# USD_PD.net
KiCad netlist of a schematic drawn in Altium Designer
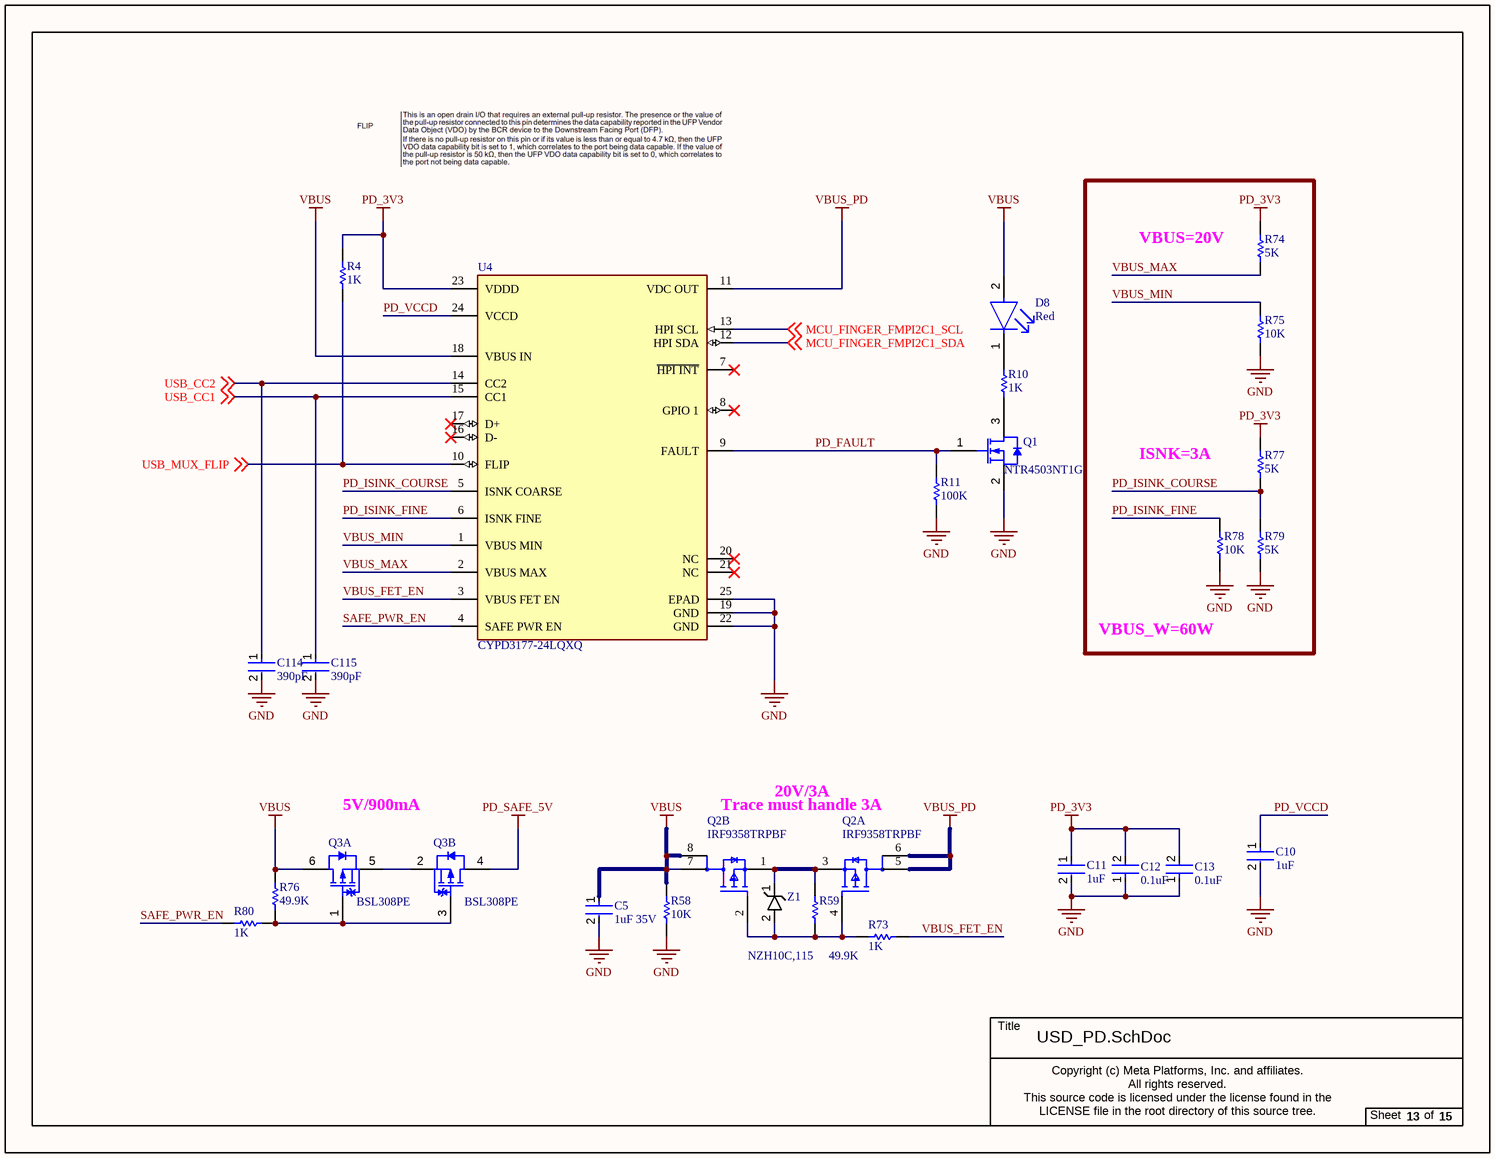
[diagram p0: USD_PD.SchDoc]

(export (version "E")
  (design (tool "Eeschema 10.0.6"))
  (components
    (comp (ref "C5")
      (value "1uF 35V")
      (footprint "FP-C1005-050-0_05-IPC_C")
      (description "Multilayer Ceramic Capacitors 1μF ±10% 35V X5R SMD 0402")
      (fields (field (name "TOLERANCE") "10%"))
      (libsource (lib "Altium Content Vault") (part "b4654b650e69147ec39a6b967a45e02"))
    )
    (comp (ref "C10")
      (value "1uF")
      (footprint "FP-CL511-IPC_C")
      (description "Cap Ceramic 1uF 10V X5R ±10% SMD 0402 +85°C Paper T/R")
      (fields (field (name "TOLERANCE") "10%"))
      (libsource (lib "Altium Content Vault") (part "b4654b650e69147ec39a6b967a45e02"))
    )
    (comp (ref "C11")
      (value "1uF")
      (footprint "FP-CL511-IPC_C")
      (description "Cap Ceramic 1uF 10V X5R ±10% SMD 0402 +85°C Paper T/R")
      (fields (field (name "TOLERANCE") "10%"))
      (libsource (lib "Altium Content Vault") (part "b4654b650e69147ec39a6b967a45e02"))
    )
    (comp (ref "C12")
      (value "0.1uF")
      (footprint "FP-CC0201-BA-MFG")
      (description "CAP CER 0.1UF 6.3V X5R 0201")
      (fields (field (name "MANUFACTURER") "Yageo") (field (name "TOLERANCE") "0.1"))
      (libsource (lib "Altium Content Vault") (part "11868f565c42a9108669ba33697ecf6"))
    )
    (comp (ref "C13")
      (value "0.1uF")
      (footprint "FP-CC0201-BA-MFG")
      (description "CAP CER 0.1UF 6.3V X5R 0201")
      (fields (field (name "MANUFACTURER") "Yageo") (field (name "TOLERANCE") "0.1"))
      (libsource (lib "Altium Content Vault") (part "11868f565c42a9108669ba33697ecf6"))
    )
    (comp (ref "C114")
      (value "390pF")
      (footprint "FP-C0402-BB-MFG")
      (description "CAP CER 390PF 50V C0G/NP0 0402")
      (fields
        (field (name "OCTOPART") "https://octopart.com/c0402c391j5gactu-kemet-13148117")
        (field (name "MANUFACTURER PART NUMBER") "C0402C391J5GACTU")
      )
      (libsource (lib "Altium Content Vault") (part "b4654b650e69147ec39a6b967a45e02"))
    )
    (comp (ref "C115")
      (value "390pF")
      (footprint "FP-C0402-BB-MFG")
      (description "CAP CER 390PF 50V C0G/NP0 0402")
      (fields
        (field (name "OCTOPART") "https://octopart.com/c0402c391j5gactu-kemet-13148117")
        (field (name "MANUFACTURER PART NUMBER") "C0402C391J5GACTU")
      )
      (libsource (lib "Altium Content Vault") (part "b4654b650e69147ec39a6b967a45e02"))
    )
    (comp (ref "D8")
      (value "Red")
      (footprint "FP-LTST-C190KRKT-MFG")
      (description "LED RED CLEAR CHIP SMD")
      (libsource (lib "Altium Content Vault") (part "8706943c75ba83719d021d2fdc84c58"))
    )
    (comp (ref "Q1")
      (value "NTR4503NT1G")
      (footprint "ONSC-SOT-23-3-318-08_V")
      (description "Power MOSFET, 30 V, 2.5 A, Single N-Channel, 3-Pin SOT-23, Pb-Free, Tape and Reel")
      (fields (field (name "MANUFACTURER") "On Semiconductor"))
      (libsource (lib "Altium Content Vault") (part "ONSC-NMOS-G1S2D3-3"))
    )
    (comp (ref "Q2")
      (value "IRF9358TRPBF")
      (footprint "FP-PG-DSO-8-IPC_A")
      (description "MOSFET 2P-CH 30V 9.2A 8SOIC")
      (libsource (lib "Altium Content Vault") (part "5e38728c795c682e8f1ce7f9b94c653"))
    )
    (comp (ref "Q3")
      (value "BSL308PE")
      (footprint "INF-PG-TSOP-6_N")
      (fields (field (name "MANUFACTURER") "Infineon"))
      (libsource (lib "Altium Content Vault") (part "INF-BSL3_2XX-PG-TSOP-6-6"))
    )
    (comp (ref "R4")
      (value "1K")
      (footprint "RESC1005X40X25NL05T05")
      (description "Chip Resistor, 1 KOhm, +/- 1%, 100 mW, -55 to 155 degC, 0402 (1005 Metric), RoHS, Tape and Reel")
      (fields (field (name "PARTNUMBER") "ERJ-2RKF1001X") (field (name "MANUFACTURER") "Basic Passives"))
      (libsource (lib "Altium Content Vault") (part "RES-2"))
    )
    (comp (ref "R10")
      (value "1K")
      (footprint "RESC1005X40X25NL05T05")
      (description "Chip Resistor, 1 KOhm, +/- 1%, 100 mW, -55 to 155 degC, 0402 (1005 Metric), RoHS, Tape and Reel")
      (fields (field (name "PARTNUMBER") "ERJ-2RKF1001X") (field (name "MANUFACTURER") "Basic Passives"))
      (libsource (lib "Altium Content Vault") (part "RES-2"))
    )
    (comp (ref "R11")
      (value "100K")
      (footprint "RESC1005X40X25NL05T10")
      (fields (field (name "PART NUMBER") "RC0402FR-07100KL") (field (name "MANUFACTURER") "Yageo / Phycomp"))
      (libsource (lib "Altium Content Vault") (part "RES"))
    )
    (comp (ref "R58")
      (value "10K")
      (footprint "RESC1005X40X25ML05T10")
      (fields (field (name "PART NUMBER") "CRCW040210K0FKEDHP") (field (name "MANUFACTURER") "Vishay Dale"))
      (libsource (lib "Altium Content Vault") (part "RES"))
    )
    (comp (ref "R59")
      (value "49.9K")
      (footprint "RESC1005X35X20LL05T10")
      (fields
        (field (name "PART NUMBER") "CPF0402B49K9E1")
        (field (name "MANUFACTURER") "TE Connectivity / AMP")
      )
      (libsource (lib "Altium Content Vault") (part "RES"))
    )
    (comp (ref "R73")
      (value "1K")
      (footprint "RESC1005X40X25NL05T05")
      (description "Chip Resistor, 1 KOhm, +/- 1%, 100 mW, -55 to 155 degC, 0402 (1005 Metric), RoHS, Tape and Reel")
      (fields (field (name "PARTNUMBER") "ERJ-2RKF1001X") (field (name "MANUFACTURER") "Basic Passives"))
      (libsource (lib "Altium Content Vault") (part "RES-2"))
    )
    (comp (ref "R74")
      (value "5K")
      (footprint "RESC1005X35X20LL05T10")
      (fields
        (field (name "MANUFACTURER") "TE Connectivity / AMP")
        (field (name "PART NUMBER") "CPF0402B5K1E1")
      )
      (libsource (lib "Altium Content Vault") (part "RES"))
    )
    (comp (ref "R75")
      (value "10K")
      (footprint "RESC1005X40X25ML05T10")
      (fields (field (name "PART NUMBER") "CRCW040210K0FKEDHP") (field (name "MANUFACTURER") "Vishay Dale"))
      (libsource (lib "Altium Content Vault") (part "RES"))
    )
    (comp (ref "R76")
      (value "49.9K")
      (footprint "RESC1005X35X20LL05T10")
      (fields
        (field (name "PART NUMBER") "CPF0402B49K9E1")
        (field (name "MANUFACTURER") "TE Connectivity / AMP")
      )
      (libsource (lib "Altium Content Vault") (part "RES"))
    )
    (comp (ref "R77")
      (value "5K")
      (footprint "RESC1005X35X20LL05T10")
      (fields
        (field (name "MANUFACTURER") "TE Connectivity / AMP")
        (field (name "PART NUMBER") "CPF0402B5K1E1")
      )
      (libsource (lib "Altium Content Vault") (part "RES"))
    )
    (comp (ref "R78")
      (value "10K")
      (footprint "RESC1005X40X25ML05T10")
      (fields (field (name "PART NUMBER") "CRCW040210K0FKEDHP") (field (name "MANUFACTURER") "Vishay Dale"))
      (libsource (lib "Altium Content Vault") (part "RES"))
    )
    (comp (ref "R79")
      (value "5K")
      (footprint "RESC1005X35X20LL05T10")
      (fields
        (field (name "MANUFACTURER") "TE Connectivity / AMP")
        (field (name "PART NUMBER") "CPF0402B5K1E1")
      )
      (libsource (lib "Altium Content Vault") (part "RES"))
    )
    (comp (ref "R80")
      (value "1K")
      (footprint "RESC1005X40X25NL05T05")
      (description "Chip Resistor, 1 KOhm, +/- 1%, 100 mW, -55 to 155 degC, 0402 (1005 Metric), RoHS, Tape and Reel")
      (fields (field (name "PARTNUMBER") "ERJ-2RKF1001X") (field (name "MANUFACTURER") "Basic Passives"))
      (libsource (lib "Altium Content Vault") (part "RES-2"))
    )
    (comp (ref "U4")
      (value "CYPD3177-24LQXQ")
      (footprint "FP-002-16934-IPC_C")
      (description "IC USB TYPE-C PORT CONTROL 24QFN")
      (libsource (lib "Altium Content Vault") (part "568390810166e80f7277aa93be1c0e6"))
    )
    (comp (ref "Z1")
      (value "NZH10C,115")
      (footprint "SamacSys:SODFL3516X120N")
      (description "Zener Diode")
      (fields (field (name "MOUSER PART NUMBER") "771-NZH10C-115"))
      (libsource (lib "SamacSys") (part "NZH10C,115"))
    )
  )
  (nets
    (net (code "1") (name "/PD_FAULT") (class "Default")
      (node (ref "Q1") (pin "1") (pinfunction "G_1") (pintype "passive"))
      (node (ref "R11") (pin "2") (pinfunction "2_2") (pintype "passive"))
      (node (ref "U4") (pin "9") (pinfunction "FAULT_9") (pintype "open_collector"))
    )
    (net (code "2") (name "/PD_ISINK_COURSE") (class "Default")
      (node (ref "R77") (pin "1") (pinfunction "1_1") (pintype "passive"))
      (node (ref "R79") (pin "2") (pinfunction "2_2") (pintype "passive"))
      (node (ref "U4") (pin "5") (pinfunction "ISNK_COARSE_5") (pintype "passive"))
    )
    (net (code "3") (name "/PD_ISINK_FINE") (class "Default")
      (node (ref "R78") (pin "1") (pinfunction "1_1") (pintype "passive"))
      (node (ref "U4") (pin "6") (pinfunction "ISNK_FINE_6") (pintype "passive"))
    )
    (net (code "4") (name "/PD_VCCD") (class "Default")
      (node (ref "C10") (pin "1") (pinfunction "1_1") (pintype "passive"))
      (node (ref "U4") (pin "24") (pinfunction "VCCD_24") (pintype "power_in"))
    )
    (net (code "5") (name "/SAFE_PWR_EN") (class "Default")
      (node (ref "R80") (pin "2") (pinfunction "2_2") (pintype "passive"))
      (node (ref "U4") (pin "4") (pinfunction "SAFE_PWR_EN_4") (pintype "passive"))
    )
    (net (code "6") (name "/VBUS_FET_EN") (class "Default")
      (node (ref "R73") (pin "1") (pinfunction "1_1") (pintype "passive"))
      (node (ref "U4") (pin "3") (pinfunction "VBUS_FET_EN_3") (pintype "passive"))
    )
    (net (code "7") (name "/VBUS_MAX") (class "Default")
      (node (ref "R74") (pin "1") (pinfunction "1_1") (pintype "passive"))
      (node (ref "U4") (pin "2") (pinfunction "VBUS_MAX_2") (pintype "passive"))
    )
    (net (code "8") (name "/VBUS_MIN") (class "Default")
      (node (ref "R75") (pin "1") (pinfunction "1_1") (pintype "passive"))
      (node (ref "U4") (pin "1") (pinfunction "VBUS_MIN_1") (pintype "passive"))
    )
    (net (code "9") (name "GND") (class "Default")
      (node (ref "C10") (pin "2") (pinfunction "2_2") (pintype "passive"))
      (node (ref "C11") (pin "2") (pinfunction "2_2") (pintype "passive"))
      (node (ref "C114") (pin "2") (pinfunction "2_2") (pintype "passive"))
      (node (ref "C115") (pin "2") (pinfunction "2_2") (pintype "passive"))
      (node (ref "C12") (pin "1") (pinfunction "1_1") (pintype "passive"))
      (node (ref "C13") (pin "1") (pinfunction "1_1") (pintype "passive"))
      (node (ref "C5") (pin "2") (pinfunction "2_2") (pintype "passive"))
      (node (ref "Q1") (pin "2") (pinfunction "S_2") (pintype "passive"))
      (node (ref "R11") (pin "1") (pinfunction "1_1") (pintype "passive"))
      (node (ref "R58") (pin "1") (pinfunction "1_1") (pintype "passive"))
      (node (ref "R75") (pin "2") (pinfunction "2_2") (pintype "passive"))
      (node (ref "R78") (pin "2") (pinfunction "2_2") (pintype "passive"))
      (node (ref "R79") (pin "1") (pinfunction "1_1") (pintype "passive"))
      (node (ref "U4") (pin "19") (pinfunction "GND_19") (pintype "power_in"))
      (node (ref "U4") (pin "22") (pinfunction "GND_22") (pintype "power_in"))
      (node (ref "U4") (pin "25") (pinfunction "EPAD_25") (pintype "power_in"))
    )
    (net (code "10") (name "MCU_FINGER_FMPI2C1_SCL") (class "Default")
      (node (ref "U4") (pin "13") (pinfunction "HPI_SCL_13") (pintype "input"))
    )
    (net (code "11") (name "MCU_FINGER_FMPI2C1_SDA") (class "Default")
      (node (ref "U4") (pin "12") (pinfunction "HPI_SDA_12") (pintype "bidirectional"))
    )
    (net (code "12") (name "Net-(D8-C)") (class "Default")
      (node (ref "D8") (pin "1") (pinfunction "C_1") (pintype "passive"))
      (node (ref "R10") (pin "2") (pinfunction "2_2") (pintype "passive"))
    )
    (net (code "13") (name "Net-(Q1-D)") (class "Default")
      (node (ref "Q1") (pin "3") (pinfunction "D_3") (pintype "passive"))
      (node (ref "R10") (pin "1") (pinfunction "1_1") (pintype "passive"))
    )
    (net (code "14") (name "Net-(Q2A-G1)") (class "Default")
      (node (ref "Q2") (pin "2") (pinfunction "G2_2") (pintype "passive"))
      (node (ref "Q2") (pin "4") (pinfunction "G1_4") (pintype "passive"))
      (node (ref "R59") (pin "1") (pinfunction "1_1") (pintype "passive"))
      (node (ref "R73") (pin "2") (pinfunction "2_2") (pintype "passive"))
      (node (ref "Z1") (pin "2") (pinfunction "A_2") (pintype "passive"))
    )
    (net (code "15") (name "Net-(Q2A-S1)") (class "Default")
      (node (ref "Q2") (pin "1") (pinfunction "S2_1") (pintype "passive"))
      (node (ref "Q2") (pin "3") (pinfunction "S1_3") (pintype "passive"))
      (node (ref "R59") (pin "2") (pinfunction "2_2") (pintype "passive"))
      (node (ref "Z1") (pin "1") (pinfunction "K_1") (pintype "passive"))
    )
    (net (code "16") (name "Net-(Q3A-GATE)") (class "Default")
      (node (ref "Q3") (pin "1") (pinfunction "GATE_1") (pintype "passive"))
      (node (ref "Q3") (pin "3") (pinfunction "GATE_3") (pintype "passive"))
      (node (ref "R76") (pin "1") (pinfunction "1_1") (pintype "passive"))
      (node (ref "R80") (pin "1") (pinfunction "1_1") (pintype "passive"))
    )
    (net (code "17") (name "Net-(Q3A-SOURCE)") (class "Default")
      (node (ref "Q3") (pin "2") (pinfunction "SOURCE_2") (pintype "passive"))
      (node (ref "Q3") (pin "5") (pinfunction "SOURCE_5") (pintype "passive"))
    )
    (net (code "18") (name "PD_3V3") (class "Default")
      (node (ref "C11") (pin "1") (pinfunction "1_1") (pintype "passive"))
      (node (ref "C12") (pin "2") (pinfunction "2_2") (pintype "passive"))
      (node (ref "C13") (pin "2") (pinfunction "2_2") (pintype "passive"))
      (node (ref "R4") (pin "1") (pinfunction "1_1") (pintype "passive"))
      (node (ref "R74") (pin "2") (pinfunction "2_2") (pintype "passive"))
      (node (ref "R77") (pin "2") (pinfunction "2_2") (pintype "passive"))
      (node (ref "U4") (pin "23") (pinfunction "VDDD_23") (pintype "power_in"))
    )
    (net (code "19") (name "PD_SAFE_5V") (class "Default")
      (node (ref "Q3") (pin "4") (pinfunction "DRAIN_4") (pintype "passive"))
    )
    (net (code "20") (name "USB_CC1") (class "Default")
      (node (ref "C115") (pin "1") (pinfunction "1_1") (pintype "passive"))
      (node (ref "U4") (pin "15") (pinfunction "CC1_15") (pintype "passive"))
    )
    (net (code "21") (name "USB_CC2") (class "Default")
      (node (ref "C114") (pin "1") (pinfunction "1_1") (pintype "passive"))
      (node (ref "U4") (pin "14") (pinfunction "CC2_14") (pintype "passive"))
    )
    (net (code "22") (name "USB_MUX_FLIP") (class "Default")
      (node (ref "R4") (pin "2") (pinfunction "2_2") (pintype "passive"))
      (node (ref "U4") (pin "10") (pinfunction "FLIP_10") (pintype "bidirectional"))
    )
    (net (code "23") (name "VBUS") (class "Default")
      (node (ref "C5") (pin "1") (pinfunction "1_1") (pintype "passive"))
      (node (ref "D8") (pin "2") (pinfunction "A_2") (pintype "passive"))
      (node (ref "Q2") (pin "7") (pinfunction "D2_7") (pintype "passive"))
      (node (ref "Q2") (pin "8") (pinfunction "D2_8") (pintype "passive"))
      (node (ref "Q3") (pin "6") (pinfunction "DRAIN_6") (pintype "passive"))
      (node (ref "R58") (pin "2") (pinfunction "2_2") (pintype "passive"))
      (node (ref "R76") (pin "2") (pinfunction "2_2") (pintype "passive"))
      (node (ref "U4") (pin "18") (pinfunction "VBUS_IN_18") (pintype "power_in"))
    )
    (net (code "24") (name "VBUS_PD") (class "Default")
      (node (ref "Q2") (pin "5") (pinfunction "D1_5") (pintype "passive"))
      (node (ref "Q2") (pin "6") (pinfunction "D1_6") (pintype "passive"))
      (node (ref "U4") (pin "11") (pinfunction "VDC_OUT_11") (pintype "passive"))
    )
    (net (code "25") (name "unconnected-(U4-D+-Pad17)") (class "Default")
      (node (ref "U4") (pin "17") (pinfunction "D+_17") (pintype "bidirectional+no_connect"))
    )
    (net (code "26") (name "unconnected-(U4-D--Pad16)") (class "Default")
      (node (ref "U4") (pin "16") (pinfunction "D-_16") (pintype "bidirectional+no_connect"))
    )
    (net (code "27") (name "unconnected-(U4-GPIO_1-Pad8)") (class "Default")
      (node (ref "U4") (pin "8") (pinfunction "GPIO_1_8") (pintype "bidirectional+no_connect"))
    )
    (net (code "28") (name "unconnected-(U4-NC-Pad20)") (class "Default")
      (node (ref "U4") (pin "20") (pinfunction "NC_20") (pintype "passive+no_connect"))
    )
    (net (code "29") (name "unconnected-(U4-NC-Pad21)") (class "Default")
      (node (ref "U4") (pin "21") (pinfunction "NC_21") (pintype "passive+no_connect"))
    )
    (net (code "30") (name "unconnected-(U4-~{HPI_INT}-Pad7)") (class "Default")
      (node (ref "U4") (pin "7") (pinfunction "~{HPI_INT}_7") (pintype "passive+no_connect"))
    )
  )
)
